# power_supplies.net
KiCad netlist of a schematic drawn in Altium Designer
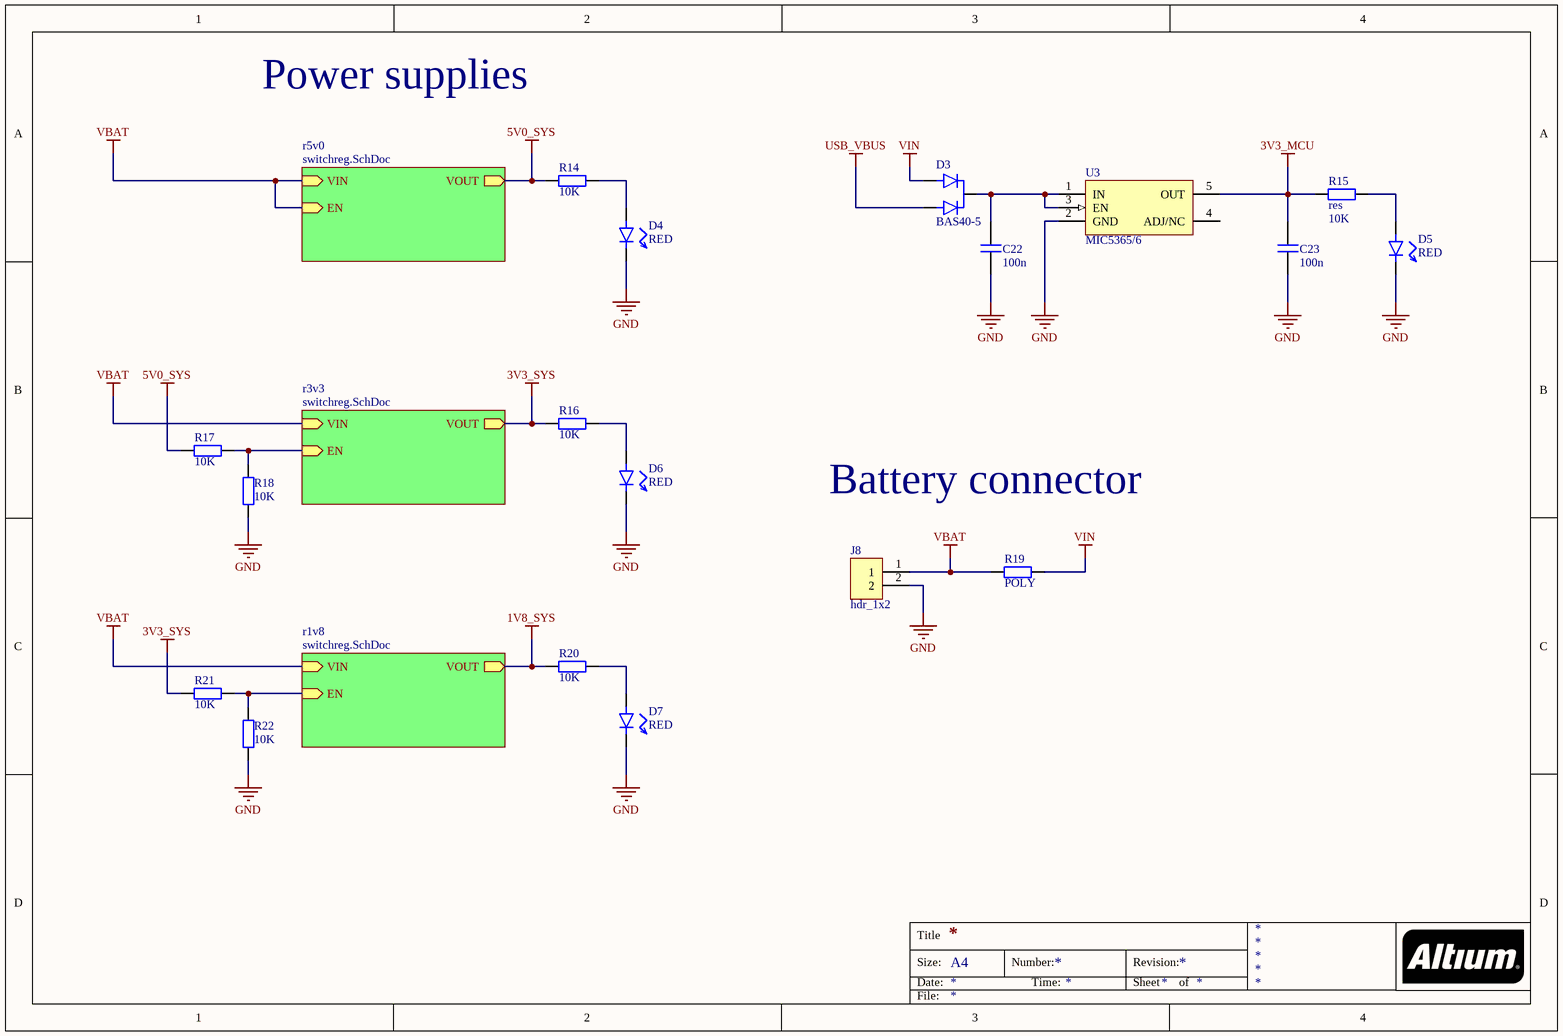
[diagram p0: power_supplies.SchDoc]

(export (version "E")
  (design (tool "Eeschema 10.0.6"))
  (components
    (comp (ref "C22")
      (value "100n")
      (footprint "CAPC1005X06N")
      (description "Capacitor")
      (fields (field (name "Comment") "cap"))
      (libsource (lib "lib_passives") (part "cap"))
    )
    (comp (ref "C23")
      (value "100n")
      (footprint "CAPC1005X06N")
      (description "Capacitor")
      (fields (field (name "Comment") "cap"))
      (libsource (lib "lib_passives") (part "cap"))
    )
    (comp (ref "D3")
      (value "BAS40-5")
      (footprint "SOT23_CC")
      (description "Diode Common Cathode")
      (libsource (lib "lib_actives") (part "diode_dual_cc"))
    )
    (comp (ref "D4")
      (value "RED")
      (footprint "CAPCP1005X06N")
      (description "LED")
      (fields (field (name "Comment") "led"))
      (libsource (lib "lib_actives") (part "led"))
    )
    (comp (ref "D5")
      (value "RED")
      (footprint "CAPCP1005X06N")
      (description "LED")
      (fields (field (name "Comment") "led"))
      (libsource (lib "lib_actives") (part "led"))
    )
    (comp (ref "D6")
      (value "RED")
      (footprint "CAPCP1005X06N")
      (description "LED")
      (fields (field (name "Comment") "led"))
      (libsource (lib "lib_actives") (part "led"))
    )
    (comp (ref "D7")
      (value "RED")
      (footprint "CAPCP1005X06N")
      (description "LED")
      (fields (field (name "Comment") "led"))
      (libsource (lib "lib_actives") (part "led"))
    )
    (comp (ref "J8")
      (value "hdr_1x2")
      (footprint "hdr_1x2_200mil")
      (description "1x2 Header")
      (libsource (lib "lib_connectors") (part "hdr_1x2"))
    )
    (comp (ref "R14")
      (value "10K")
      (footprint "RESC1005X04N")
      (description "Resistor")
      (fields (field (name "Comment") "res"))
      (libsource (lib "lib_passives") (part "res"))
    )
    (comp (ref "R15")
      (value "res")
      (footprint "RESC1005X04N")
      (description "Resistor")
      (fields (field (name "ALTIUM_VALUE") "10K"))
      (libsource (lib "lib_passives") (part "res"))
    )
    (comp (ref "R16")
      (value "10K")
      (footprint "RESC1005X04N")
      (description "Resistor")
      (fields (field (name "Comment") "res"))
      (libsource (lib "lib_passives") (part "res"))
    )
    (comp (ref "R17")
      (value "10K")
      (footprint "RESC1005X04N")
      (description "Resistor")
      (fields (field (name "Comment") "res"))
      (libsource (lib "lib_passives") (part "res"))
    )
    (comp (ref "R18")
      (value "10K")
      (footprint "RESC1005X04N")
      (description "Resistor")
      (fields (field (name "Comment") "res"))
      (libsource (lib "") (part "res_1"))
    )
    (comp (ref "R19")
      (value "POLY")
      (footprint "RESC2012X06N")
      (description "Resistor")
      (fields (field (name "Comment") "res"))
      (libsource (lib "lib_passives") (part "res"))
    )
    (comp (ref "R20")
      (value "10K")
      (footprint "RESC1005X04N")
      (description "Resistor")
      (fields (field (name "Comment") "res"))
      (libsource (lib "lib_passives") (part "res"))
    )
    (comp (ref "R21")
      (value "10K")
      (footprint "RESC1005X04N")
      (description "Resistor")
      (fields (field (name "Comment") "res"))
      (libsource (lib "lib_passives") (part "res"))
    )
    (comp (ref "R22")
      (value "10K")
      (footprint "RESC1005X04N")
      (description "Resistor")
      (fields (field (name "Comment") "res"))
      (libsource (lib "") (part "res_1"))
    )
    (comp (ref "U3")
      (value "MIC5365/6")
      (footprint "SOT65P210X110-5N")
      (description "5pin voltage regulator")
      (libsource (lib "lib_microchip") (part "mic5365"))
    )
  )
  (nets
    (net (code "1") (name "/EN") (class "Default")
      (node (ref "R17") (pin "2") (pinfunction "2_2") (pintype "passive"))
      (node (ref "R18") (pin "2") (pinfunction "2_2") (pintype "passive"))
    )
    (net (code "2") (name "/EN_1") (class "Default")
      (node (ref "R21") (pin "2") (pinfunction "2_2") (pintype "passive"))
      (node (ref "R22") (pin "2") (pinfunction "2_2") (pintype "passive"))
    )
    (net (code "3") (name "1V8_SYS") (class "Default")
      (node (ref "R20") (pin "1") (pinfunction "1_1") (pintype "passive"))
    )
    (net (code "4") (name "3V3_MCU") (class "Default")
      (node (ref "C23") (pin "2") (pinfunction "2_2") (pintype "passive"))
      (node (ref "R15") (pin "1") (pinfunction "1_1") (pintype "passive"))
      (node (ref "U3") (pin "5") (pinfunction "OUT_5") (pintype "power_in"))
    )
    (net (code "5") (name "3V3_SYS") (class "Default")
      (node (ref "R16") (pin "1") (pinfunction "1_1") (pintype "passive"))
      (node (ref "R21") (pin "1") (pinfunction "1_1") (pintype "passive"))
    )
    (net (code "6") (name "5V0_SYS") (class "Default")
      (node (ref "R14") (pin "1") (pinfunction "1_1") (pintype "passive"))
      (node (ref "R17") (pin "1") (pinfunction "1_1") (pintype "passive"))
    )
    (net (code "7") (name "GND") (class "Default")
      (node (ref "C22") (pin "1") (pinfunction "1_1") (pintype "passive"))
      (node (ref "C23") (pin "1") (pinfunction "1_1") (pintype "passive"))
      (node (ref "D4") (pin "C") (pinfunction "C_C") (pintype "passive"))
      (node (ref "D5") (pin "C") (pinfunction "C_C") (pintype "passive"))
      (node (ref "D6") (pin "C") (pinfunction "C_C") (pintype "passive"))
      (node (ref "D7") (pin "C") (pinfunction "C_C") (pintype "passive"))
      (node (ref "J8") (pin "2") (pinfunction "2_2") (pintype "passive"))
      (node (ref "R18") (pin "1") (pinfunction "1_1") (pintype "passive"))
      (node (ref "R22") (pin "1") (pinfunction "1_1") (pintype "passive"))
      (node (ref "U3") (pin "2") (pinfunction "GND_2") (pintype "power_in"))
    )
    (net (code "8") (name "Net-(D4-PadA)") (class "Default")
      (node (ref "D4") (pin "A") (pinfunction "A_A") (pintype "passive"))
      (node (ref "R14") (pin "2") (pinfunction "2_2") (pintype "passive"))
    )
    (net (code "9") (name "Net-(D5-PadA)") (class "Default")
      (node (ref "D5") (pin "A") (pinfunction "A_A") (pintype "passive"))
      (node (ref "R15") (pin "2") (pinfunction "2_2") (pintype "passive"))
    )
    (net (code "10") (name "Net-(D6-PadA)") (class "Default")
      (node (ref "D6") (pin "A") (pinfunction "A_A") (pintype "passive"))
      (node (ref "R16") (pin "2") (pinfunction "2_2") (pintype "passive"))
    )
    (net (code "11") (name "Net-(D7-PadA)") (class "Default")
      (node (ref "D7") (pin "A") (pinfunction "A_A") (pintype "passive"))
      (node (ref "R20") (pin "2") (pinfunction "2_2") (pintype "passive"))
    )
    (net (code "12") (name "Net-(U3-EN)") (class "Default")
      (node (ref "C22") (pin "2") (pinfunction "2_2") (pintype "passive"))
      (node (ref "D3") (pin "C") (pinfunction "C_C") (pintype "passive"))
      (node (ref "U3") (pin "1") (pinfunction "IN_1") (pintype "power_in"))
      (node (ref "U3") (pin "3") (pinfunction "EN_3") (pintype "input"))
    )
    (net (code "13") (name "USB_VBUS") (class "Default")
      (node (ref "D3") (pin "A2") (pinfunction "A2_A2") (pintype "passive"))
    )
    (net (code "14") (name "VBAT") (class "Default")
      (node (ref "J8") (pin "1") (pinfunction "1_1") (pintype "passive"))
      (node (ref "R19") (pin "1") (pinfunction "1_1") (pintype "passive"))
    )
    (net (code "15") (name "VIN") (class "Default")
      (node (ref "D3") (pin "A1") (pinfunction "A1_A1") (pintype "passive"))
      (node (ref "R19") (pin "2") (pinfunction "2_2") (pintype "passive"))
    )
    (net (code "16") (name "unconnected-(U3-ADJ{slash}NC-Pad4)") (class "Default")
      (node (ref "U3") (pin "4") (pinfunction "ADJ/NC_4") (pintype "passive"))
    )
  )
)
